# Camera_Board.net
KiCad netlist of a schematic drawn in Altium Designer
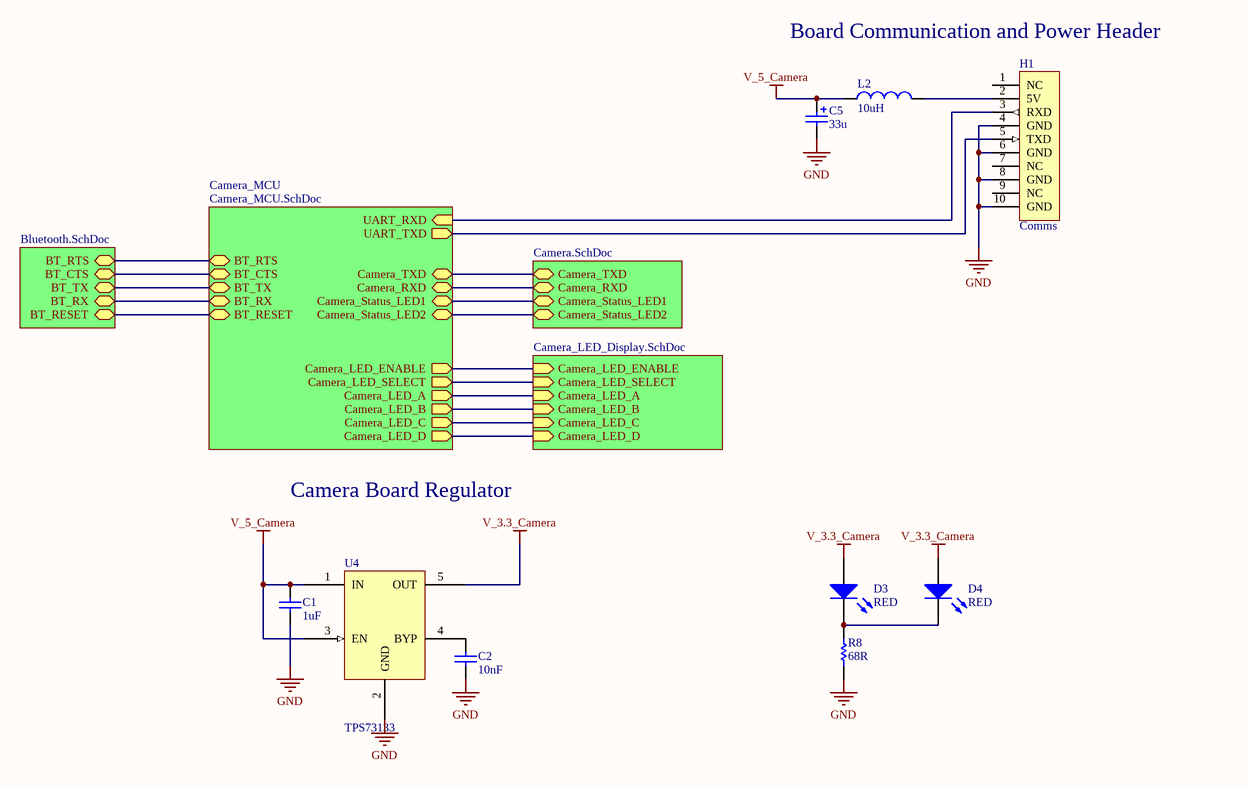
[diagram p0: Camera_Board.SchDoc]

(export (version "E")
  (design (tool "Eeschema 10.0.6"))
  (components
    (comp (ref "C1")
      (value "1uF")
      (footprint "0603")
      (description "CAP CER 1.0UF 50V X7R 0603")
      (fields (field (name "MANUFACTURER") "Taiyo Yuden") (field (name "PART NUMBER") "CP_1uF_50V_0603"))
      (libsource (lib "ENEL429_4") (part "CP_1uF_50V_0603"))
    )
    (comp (ref "C2")
      (value "10nF")
      (footprint "0603")
      (description "CAP CER 10000PF 100V X7R 0603")
      (fields (field (name "MANUFACTURER") "Taiyo Yuden") (field (name "PART NUMBER") "CP_10nF 0603"))
      (libsource (lib "ENEL429_4") (part "CP_10nF 0603"))
    )
    (comp (ref "C5")
      (value "33u")
      (footprint "6032")
      (description "CAP TANT 33UF 20V 10% SMD")
      (fields (field (name "MANUFACTURER") "Vishay") (field (name "PART NUMBER") "CP_TANT_33UF_20V"))
      (libsource (lib "ENEL429_4") (part "CP_TANT_33UF_20V"))
    )
    (comp (ref "D3")
      (value "RED")
      (footprint "Diode_0805")
      (description "Red LED 0805")
      (fields (field (name "MANUFACTURER") "Vishay") (field (name "PART NUMBER") "DL_LED Red 0805"))
      (libsource (lib "ENEL429_4") (part "DL_LED Red 0805"))
    )
    (comp (ref "D4")
      (value "RED")
      (footprint "Diode_0805")
      (description "Red LED 0805")
      (fields (field (name "MANUFACTURER") "Vishay") (field (name "PART NUMBER") "DL_LED Red 0805"))
      (libsource (lib "ENEL429_4") (part "DL_LED Red 0805"))
    )
    (comp (ref "H1")
      (value "Comms")
      (footprint "918510x323")
      (description "Header, IDC 10-Pin")
      (fields (field (name "PUBLISHER") "Altium Limited"))
      (libsource (lib "Wacky_1") (part "Header 10"))
    )
    (comp (ref "L2")
      (value "10uH")
      (footprint "WE-PD")
      (description "INDUCTOR POWER 10UH 2.0A SMD")
      (fields
        (field (name "MANUFACTURER") "Wurth Electronics Inc")
        (field (name "PART NUMBER") "IN_10uH 2A SMT")
      )
      (libsource (lib "ENEL429_4") (part "IN_10uH 2A SMT"))
    )
    (comp (ref "R8")
      (value "68R")
      (footprint "0603")
      (description "RES 68 OHM 1/10W 1% 0603 SMD")
      (fields (field (name "MANUFACTURER") "Yageo") (field (name "PART NUMBER") "RS_68R 0603"))
      (libsource (lib "ENEL429_4") (part "RS_68R 0603"))
    )
    (comp (ref "U4")
      (value "TPS73133")
      (footprint "DBV005")
      (description "150mA 3.3V linear regulator with 30mV dropout")
      (fields (field (name "MANUFACTURER") "Texas Instruments") (field (name "PART NUMBER") "IC_TPS73133"))
      (libsource (lib "ENEL429_4") (part "IC_TPS73133"))
    )
  )
  (nets
    (net (code "16") (name "/UART_RXD") (class "Default")
      (node (ref "H1") (pin "3") (pinfunction "RXD_3") (pintype "output"))
    )
    (net (code "17") (name "/UART_TXD") (class "Default")
      (node (ref "H1") (pin "5") (pinfunction "TXD_5") (pintype "input"))
    )
    (net (code "18") (name "GND") (class "Default")
      (node (ref "C1") (pin "1") (pinfunction "1_1") (pintype "passive"))
      (node (ref "C2") (pin "1") (pinfunction "1_1") (pintype "passive"))
      (node (ref "C5") (pin "2") (pinfunction "2_2") (pintype "passive"))
      (node (ref "H1") (pin "10") (pinfunction "GND_10") (pintype "power_in"))
      (node (ref "H1") (pin "4") (pinfunction "GND_4") (pintype "power_in"))
      (node (ref "H1") (pin "6") (pinfunction "GND_6") (pintype "power_in"))
      (node (ref "H1") (pin "8") (pinfunction "GND_8") (pintype "power_in"))
      (node (ref "R8") (pin "1") (pinfunction "1_1") (pintype "passive"))
      (node (ref "U4") (pin "2") (pinfunction "GND_2") (pintype "power_in"))
    )
    (net (code "19") (name "Net-(D3-K)") (class "Default")
      (node (ref "D3") (pin "2") (pinfunction "K_2") (pintype "passive"))
      (node (ref "D4") (pin "2") (pinfunction "K_2") (pintype "passive"))
      (node (ref "R8") (pin "2") (pinfunction "2_2") (pintype "passive"))
    )
    (net (code "20") (name "Net-(H1-5V)") (class "Default")
      (node (ref "H1") (pin "2") (pinfunction "5V_2") (pintype "power_in"))
      (node (ref "L2") (pin "2") (pinfunction "2_2") (pintype "passive"))
    )
    (net (code "21") (name "Net-(U4-BYP)") (class "Default")
      (node (ref "C2") (pin "2") (pinfunction "2_2") (pintype "passive"))
      (node (ref "U4") (pin "4") (pinfunction "BYP_4") (pintype "passive"))
    )
    (net (code "22") (name "V_3.3_Camera") (class "Default")
      (node (ref "D3") (pin "1") (pinfunction "A_1") (pintype "passive"))
      (node (ref "D4") (pin "1") (pinfunction "A_1") (pintype "passive"))
      (node (ref "U4") (pin "5") (pinfunction "OUT_5") (pintype "power_in"))
    )
    (net (code "23") (name "V_5_Camera") (class "Default")
      (node (ref "C1") (pin "2") (pinfunction "2_2") (pintype "passive"))
      (node (ref "C5") (pin "1") (pinfunction "1_1") (pintype "passive"))
      (node (ref "L2") (pin "1") (pinfunction "1_1") (pintype "passive"))
      (node (ref "U4") (pin "1") (pinfunction "IN_1") (pintype "power_in"))
      (node (ref "U4") (pin "3") (pinfunction "EN_3") (pintype "input"))
    )
    (net (code "24") (name "unconnected-(H1-NC-Pad1)") (class "Default")
      (node (ref "H1") (pin "1") (pinfunction "NC_1") (pintype "passive"))
    )
    (net (code "25") (name "unconnected-(H1-NC-Pad7)") (class "Default")
      (node (ref "H1") (pin "7") (pinfunction "NC_7") (pintype "passive"))
    )
    (net (code "26") (name "unconnected-(H1-NC-Pad9)") (class "Default")
      (node (ref "H1") (pin "9") (pinfunction "NC_9") (pintype "passive"))
    )
  )
)
